# control_master.net
KiCad netlist of a schematic drawn in EAGLE
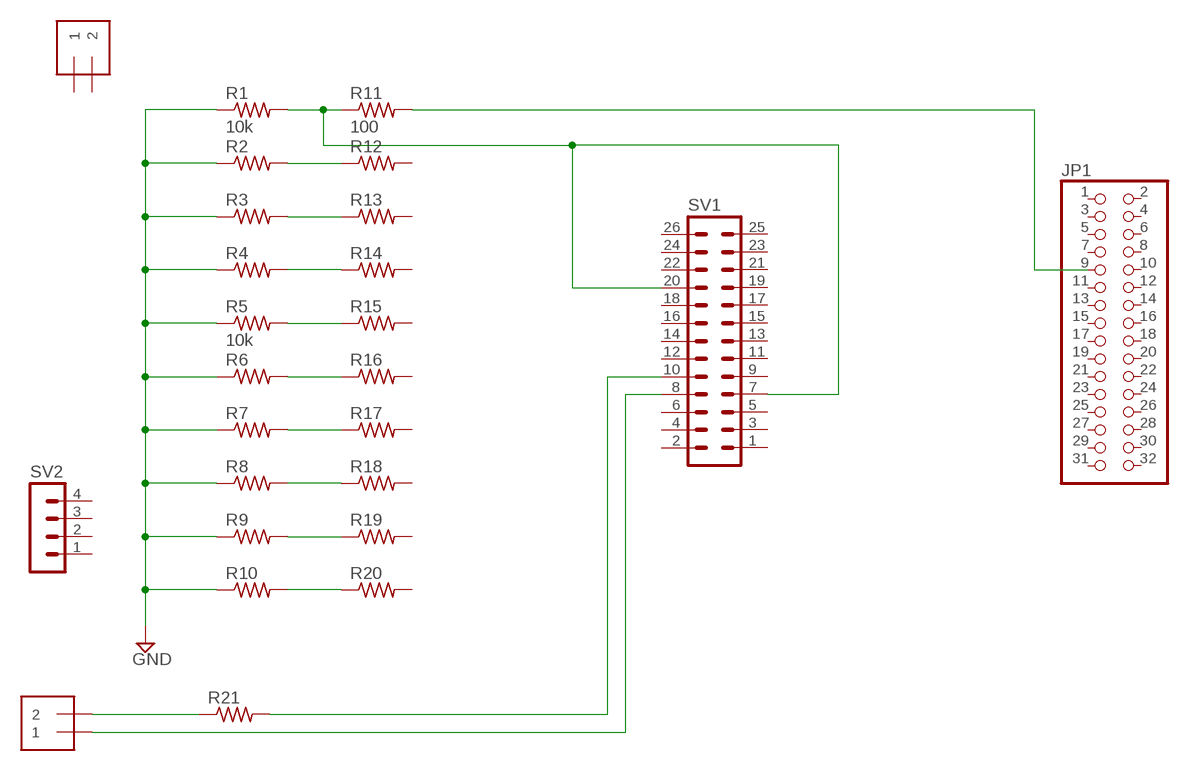
[diagram p0: schematic, sheet 1]

(export (version "E")
  (design (tool "Eeschema 10.0.6"))
  (components
    (comp (ref "J1")
      (value "1X2-3.5MM")
      (footprint "eagle-import:1X2-3.5MM")
      (libsource (lib "eagle-import") (part "1X2-3.5MM"))
    )
    (comp (ref "J2")
      (value "1X2-3.5MM")
      (footprint "eagle-import:1X2-3.5MM")
      (libsource (lib "eagle-import") (part "1X2-3.5MM"))
    )
    (comp (ref "JP1")
      (value "PINHD-2X16")
      (footprint "eagle-import:2X16")
      (libsource (lib "eagle-import") (part "PINHD-2X16"))
    )
    (comp (ref "R1")
      (value "10k")
      (footprint "eagle-import:0207_12")
      (libsource (lib "eagle-import") (part "R-US_0207/12"))
    )
    (comp (ref "R2")
      (value "R-US_0207/12")
      (footprint "eagle-import:0207_12")
      (libsource (lib "eagle-import") (part "R-US_0207/12"))
    )
    (comp (ref "R3")
      (value "R-US_0207/12")
      (footprint "eagle-import:0207_12")
      (libsource (lib "eagle-import") (part "R-US_0207/12"))
    )
    (comp (ref "R4")
      (value "R-US_0207/12")
      (footprint "eagle-import:0207_12")
      (libsource (lib "eagle-import") (part "R-US_0207/12"))
    )
    (comp (ref "R5")
      (value "10k")
      (footprint "eagle-import:0207_12")
      (libsource (lib "eagle-import") (part "R-US_0207/12"))
    )
    (comp (ref "R6")
      (value "R-US_0207/12")
      (footprint "eagle-import:0207_12")
      (libsource (lib "eagle-import") (part "R-US_0207/12"))
    )
    (comp (ref "R7")
      (value "R-US_0207/12")
      (footprint "eagle-import:0207_12")
      (libsource (lib "eagle-import") (part "R-US_0207/12"))
    )
    (comp (ref "R8")
      (value "R-US_0207/12")
      (footprint "eagle-import:0207_12")
      (libsource (lib "eagle-import") (part "R-US_0207/12"))
    )
    (comp (ref "R9")
      (value "R-US_0207/12")
      (footprint "eagle-import:0207_12")
      (libsource (lib "eagle-import") (part "R-US_0207/12"))
    )
    (comp (ref "R10")
      (value "R-US_0207/12")
      (footprint "eagle-import:0207_12")
      (libsource (lib "eagle-import") (part "R-US_0207/12"))
    )
    (comp (ref "R11")
      (value "100")
      (footprint "eagle-import:0207_12")
      (libsource (lib "eagle-import") (part "R-US_0207/12"))
    )
    (comp (ref "R12")
      (value "R-US_0207/12")
      (footprint "eagle-import:0207_12")
      (libsource (lib "eagle-import") (part "R-US_0207/12"))
    )
    (comp (ref "R13")
      (value "R-US_0207/12")
      (footprint "eagle-import:0207_12")
      (libsource (lib "eagle-import") (part "R-US_0207/12"))
    )
    (comp (ref "R14")
      (value "R-US_0207/12")
      (footprint "eagle-import:0207_12")
      (libsource (lib "eagle-import") (part "R-US_0207/12"))
    )
    (comp (ref "R15")
      (value "R-US_0207/12")
      (footprint "eagle-import:0207_12")
      (libsource (lib "eagle-import") (part "R-US_0207/12"))
    )
    (comp (ref "R16")
      (value "R-US_0207/12")
      (footprint "eagle-import:0207_12")
      (libsource (lib "eagle-import") (part "R-US_0207/12"))
    )
    (comp (ref "R17")
      (value "R-US_0207/12")
      (footprint "eagle-import:0207_12")
      (libsource (lib "eagle-import") (part "R-US_0207/12"))
    )
    (comp (ref "R18")
      (value "R-US_0207/12")
      (footprint "eagle-import:0207_12")
      (libsource (lib "eagle-import") (part "R-US_0207/12"))
    )
    (comp (ref "R19")
      (value "R-US_0207/12")
      (footprint "eagle-import:0207_12")
      (libsource (lib "eagle-import") (part "R-US_0207/12"))
    )
    (comp (ref "R20")
      (value "R-US_0207/12")
      (footprint "eagle-import:0207_12")
      (libsource (lib "eagle-import") (part "R-US_0207/12"))
    )
    (comp (ref "R21")
      (value "R-US_0207/12")
      (footprint "eagle-import:0207_12")
      (libsource (lib "eagle-import") (part "R-US_0207/12"))
    )
    (comp (ref "SV1")
      (value "MA13-2")
      (footprint "eagle-import:MA13-2")
      (libsource (lib "eagle-import") (part "MA13-2"))
    )
    (comp (ref "SV2")
      (value "MA04-1")
      (footprint "eagle-import:MA04-1")
      (libsource (lib "eagle-import") (part "MA04-1"))
    )
  )
  (nets
    (net (code "1") (name "GND") (class "Default")
      (node (ref "R1") (pin "1") (pinfunction "1_1") (pintype "passive"))
      (node (ref "R10") (pin "1") (pinfunction "1_1") (pintype "passive"))
      (node (ref "R2") (pin "1") (pinfunction "1_1") (pintype "passive"))
      (node (ref "R3") (pin "1") (pinfunction "1_1") (pintype "passive"))
      (node (ref "R4") (pin "1") (pinfunction "1_1") (pintype "passive"))
      (node (ref "R5") (pin "1") (pinfunction "1_1") (pintype "passive"))
      (node (ref "R6") (pin "1") (pinfunction "1_1") (pintype "passive"))
      (node (ref "R7") (pin "1") (pinfunction "1_1") (pintype "passive"))
      (node (ref "R8") (pin "1") (pinfunction "1_1") (pintype "passive"))
      (node (ref "R9") (pin "1") (pinfunction "1_1") (pintype "passive"))
    )
    (net (code "2") (name "Net-(J1-Pad1)") (class "Default")
      (node (ref "J1") (pin "1") (pinfunction "1_1") (pintype "passive"))
      (node (ref "SV1") (pin "8") (pinfunction "8_8") (pintype "passive"))
    )
    (net (code "3") (name "Net-(J1-Pad2)") (class "Default")
      (node (ref "J1") (pin "2") (pinfunction "2_2") (pintype "passive"))
      (node (ref "R21") (pin "1") (pinfunction "1_1") (pintype "passive"))
    )
    (net (code "4") (name "Net-(JP1-Pad9)") (class "Default")
      (node (ref "JP1") (pin "9") (pinfunction "9_9") (pintype "passive"))
      (node (ref "R11") (pin "2") (pinfunction "2_2") (pintype "passive"))
    )
    (net (code "5") (name "Net-(R1-Pad2)") (class "Default")
      (node (ref "R1") (pin "2") (pinfunction "2_2") (pintype "passive"))
      (node (ref "R11") (pin "1") (pinfunction "1_1") (pintype "passive"))
      (node (ref "SV1") (pin "20") (pinfunction "20_20") (pintype "passive"))
      (node (ref "SV1") (pin "7") (pinfunction "7_7") (pintype "passive"))
    )
    (net (code "6") (name "Net-(R10-Pad2)") (class "Default")
      (node (ref "R10") (pin "2") (pinfunction "2_2") (pintype "passive"))
      (node (ref "R20") (pin "1") (pinfunction "1_1") (pintype "passive"))
    )
    (net (code "7") (name "Net-(R12-Pad1)") (class "Default")
      (node (ref "R12") (pin "1") (pinfunction "1_1") (pintype "passive"))
      (node (ref "R2") (pin "2") (pinfunction "2_2") (pintype "passive"))
    )
    (net (code "8") (name "Net-(R13-Pad1)") (class "Default")
      (node (ref "R13") (pin "1") (pinfunction "1_1") (pintype "passive"))
      (node (ref "R3") (pin "2") (pinfunction "2_2") (pintype "passive"))
    )
    (net (code "9") (name "Net-(R14-Pad1)") (class "Default")
      (node (ref "R14") (pin "1") (pinfunction "1_1") (pintype "passive"))
      (node (ref "R4") (pin "2") (pinfunction "2_2") (pintype "passive"))
    )
    (net (code "10") (name "Net-(R15-Pad1)") (class "Default")
      (node (ref "R15") (pin "1") (pinfunction "1_1") (pintype "passive"))
      (node (ref "R5") (pin "2") (pinfunction "2_2") (pintype "passive"))
    )
    (net (code "11") (name "Net-(R16-Pad1)") (class "Default")
      (node (ref "R16") (pin "1") (pinfunction "1_1") (pintype "passive"))
      (node (ref "R6") (pin "2") (pinfunction "2_2") (pintype "passive"))
    )
    (net (code "12") (name "Net-(R17-Pad1)") (class "Default")
      (node (ref "R17") (pin "1") (pinfunction "1_1") (pintype "passive"))
      (node (ref "R7") (pin "2") (pinfunction "2_2") (pintype "passive"))
    )
    (net (code "13") (name "Net-(R18-Pad1)") (class "Default")
      (node (ref "R18") (pin "1") (pinfunction "1_1") (pintype "passive"))
      (node (ref "R8") (pin "2") (pinfunction "2_2") (pintype "passive"))
    )
    (net (code "14") (name "Net-(R19-Pad1)") (class "Default")
      (node (ref "R19") (pin "1") (pinfunction "1_1") (pintype "passive"))
      (node (ref "R9") (pin "2") (pinfunction "2_2") (pintype "passive"))
    )
    (net (code "15") (name "Net-(R21-Pad2)") (class "Default")
      (node (ref "R21") (pin "2") (pinfunction "2_2") (pintype "passive"))
      (node (ref "SV1") (pin "10") (pinfunction "10_10") (pintype "passive"))
    )
    (net (code "16") (name "unconnected-(J2-Pad1)") (class "Default")
      (node (ref "J2") (pin "1") (pinfunction "1_1") (pintype "passive"))
    )
    (net (code "17") (name "unconnected-(J2-Pad2)") (class "Default")
      (node (ref "J2") (pin "2") (pinfunction "2_2") (pintype "passive"))
    )
    (net (code "18") (name "unconnected-(JP1-Pad1)") (class "Default")
      (node (ref "JP1") (pin "1") (pinfunction "1_1") (pintype "passive"))
    )
    (net (code "19") (name "unconnected-(JP1-Pad2)") (class "Default")
      (node (ref "JP1") (pin "2") (pinfunction "2_2") (pintype "passive"))
    )
    (net (code "20") (name "unconnected-(JP1-Pad3)") (class "Default")
      (node (ref "JP1") (pin "3") (pinfunction "3_3") (pintype "passive"))
    )
    (net (code "21") (name "unconnected-(JP1-Pad4)") (class "Default")
      (node (ref "JP1") (pin "4") (pinfunction "4_4") (pintype "passive"))
    )
    (net (code "22") (name "unconnected-(JP1-Pad5)") (class "Default")
      (node (ref "JP1") (pin "5") (pinfunction "5_5") (pintype "passive"))
    )
    (net (code "23") (name "unconnected-(JP1-Pad6)") (class "Default")
      (node (ref "JP1") (pin "6") (pinfunction "6_6") (pintype "passive"))
    )
    (net (code "24") (name "unconnected-(JP1-Pad7)") (class "Default")
      (node (ref "JP1") (pin "7") (pinfunction "7_7") (pintype "passive"))
    )
    (net (code "25") (name "unconnected-(JP1-Pad8)") (class "Default")
      (node (ref "JP1") (pin "8") (pinfunction "8_8") (pintype "passive"))
    )
    (net (code "26") (name "unconnected-(JP1-Pad10)") (class "Default")
      (node (ref "JP1") (pin "10") (pinfunction "10_10") (pintype "passive"))
    )
    (net (code "27") (name "unconnected-(JP1-Pad11)") (class "Default")
      (node (ref "JP1") (pin "11") (pinfunction "11_11") (pintype "passive"))
    )
    (net (code "28") (name "unconnected-(JP1-Pad12)") (class "Default")
      (node (ref "JP1") (pin "12") (pinfunction "12_12") (pintype "passive"))
    )
    (net (code "29") (name "unconnected-(JP1-Pad13)") (class "Default")
      (node (ref "JP1") (pin "13") (pinfunction "13_13") (pintype "passive"))
    )
    (net (code "30") (name "unconnected-(JP1-Pad14)") (class "Default")
      (node (ref "JP1") (pin "14") (pinfunction "14_14") (pintype "passive"))
    )
    (net (code "31") (name "unconnected-(JP1-Pad15)") (class "Default")
      (node (ref "JP1") (pin "15") (pinfunction "15_15") (pintype "passive"))
    )
    (net (code "32") (name "unconnected-(JP1-Pad16)") (class "Default")
      (node (ref "JP1") (pin "16") (pinfunction "16_16") (pintype "passive"))
    )
    (net (code "33") (name "unconnected-(JP1-Pad17)") (class "Default")
      (node (ref "JP1") (pin "17") (pinfunction "17_17") (pintype "passive"))
    )
    (net (code "34") (name "unconnected-(JP1-Pad18)") (class "Default")
      (node (ref "JP1") (pin "18") (pinfunction "18_18") (pintype "passive"))
    )
    (net (code "35") (name "unconnected-(JP1-Pad19)") (class "Default")
      (node (ref "JP1") (pin "19") (pinfunction "19_19") (pintype "passive"))
    )
    (net (code "36") (name "unconnected-(JP1-Pad20)") (class "Default")
      (node (ref "JP1") (pin "20") (pinfunction "20_20") (pintype "passive"))
    )
    (net (code "37") (name "unconnected-(JP1-Pad21)") (class "Default")
      (node (ref "JP1") (pin "21") (pinfunction "21_21") (pintype "passive"))
    )
    (net (code "38") (name "unconnected-(JP1-Pad22)") (class "Default")
      (node (ref "JP1") (pin "22") (pinfunction "22_22") (pintype "passive"))
    )
    (net (code "39") (name "unconnected-(JP1-Pad23)") (class "Default")
      (node (ref "JP1") (pin "23") (pinfunction "23_23") (pintype "passive"))
    )
    (net (code "40") (name "unconnected-(JP1-Pad24)") (class "Default")
      (node (ref "JP1") (pin "24") (pinfunction "24_24") (pintype "passive"))
    )
    (net (code "41") (name "unconnected-(JP1-Pad25)") (class "Default")
      (node (ref "JP1") (pin "25") (pinfunction "25_25") (pintype "passive"))
    )
    (net (code "42") (name "unconnected-(JP1-Pad26)") (class "Default")
      (node (ref "JP1") (pin "26") (pinfunction "26_26") (pintype "passive"))
    )
    (net (code "43") (name "unconnected-(JP1-Pad27)") (class "Default")
      (node (ref "JP1") (pin "27") (pinfunction "27_27") (pintype "passive"))
    )
    (net (code "44") (name "unconnected-(JP1-Pad28)") (class "Default")
      (node (ref "JP1") (pin "28") (pinfunction "28_28") (pintype "passive"))
    )
    (net (code "45") (name "unconnected-(JP1-Pad29)") (class "Default")
      (node (ref "JP1") (pin "29") (pinfunction "29_29") (pintype "passive"))
    )
    (net (code "46") (name "unconnected-(JP1-Pad30)") (class "Default")
      (node (ref "JP1") (pin "30") (pinfunction "30_30") (pintype "passive"))
    )
    (net (code "47") (name "unconnected-(JP1-Pad31)") (class "Default")
      (node (ref "JP1") (pin "31") (pinfunction "31_31") (pintype "passive"))
    )
    (net (code "48") (name "unconnected-(JP1-Pad32)") (class "Default")
      (node (ref "JP1") (pin "32") (pinfunction "32_32") (pintype "passive"))
    )
    (net (code "49") (name "unconnected-(R12-Pad2)") (class "Default")
      (node (ref "R12") (pin "2") (pinfunction "2_2") (pintype "passive"))
    )
    (net (code "50") (name "unconnected-(R13-Pad2)") (class "Default")
      (node (ref "R13") (pin "2") (pinfunction "2_2") (pintype "passive"))
    )
    (net (code "51") (name "unconnected-(R14-Pad2)") (class "Default")
      (node (ref "R14") (pin "2") (pinfunction "2_2") (pintype "passive"))
    )
    (net (code "52") (name "unconnected-(R15-Pad2)") (class "Default")
      (node (ref "R15") (pin "2") (pinfunction "2_2") (pintype "passive"))
    )
    (net (code "53") (name "unconnected-(R16-Pad2)") (class "Default")
      (node (ref "R16") (pin "2") (pinfunction "2_2") (pintype "passive"))
    )
    (net (code "54") (name "unconnected-(R17-Pad2)") (class "Default")
      (node (ref "R17") (pin "2") (pinfunction "2_2") (pintype "passive"))
    )
    (net (code "55") (name "unconnected-(R18-Pad2)") (class "Default")
      (node (ref "R18") (pin "2") (pinfunction "2_2") (pintype "passive"))
    )
    (net (code "56") (name "unconnected-(R19-Pad2)") (class "Default")
      (node (ref "R19") (pin "2") (pinfunction "2_2") (pintype "passive"))
    )
    (net (code "57") (name "unconnected-(R20-Pad2)") (class "Default")
      (node (ref "R20") (pin "2") (pinfunction "2_2") (pintype "passive"))
    )
    (net (code "58") (name "unconnected-(SV1-Pad1)") (class "Default")
      (node (ref "SV1") (pin "1") (pinfunction "1_1") (pintype "passive"))
    )
    (net (code "59") (name "unconnected-(SV1-Pad2)") (class "Default")
      (node (ref "SV1") (pin "2") (pinfunction "2_2") (pintype "passive"))
    )
    (net (code "60") (name "unconnected-(SV1-Pad3)") (class "Default")
      (node (ref "SV1") (pin "3") (pinfunction "3_3") (pintype "passive"))
    )
    (net (code "61") (name "unconnected-(SV1-Pad4)") (class "Default")
      (node (ref "SV1") (pin "4") (pinfunction "4_4") (pintype "passive"))
    )
    (net (code "62") (name "unconnected-(SV1-Pad5)") (class "Default")
      (node (ref "SV1") (pin "5") (pinfunction "5_5") (pintype "passive"))
    )
    (net (code "63") (name "unconnected-(SV1-Pad6)") (class "Default")
      (node (ref "SV1") (pin "6") (pinfunction "6_6") (pintype "passive"))
    )
    (net (code "64") (name "unconnected-(SV1-Pad9)") (class "Default")
      (node (ref "SV1") (pin "9") (pinfunction "9_9") (pintype "passive"))
    )
    (net (code "65") (name "unconnected-(SV1-Pad11)") (class "Default")
      (node (ref "SV1") (pin "11") (pinfunction "11_11") (pintype "passive"))
    )
    (net (code "66") (name "unconnected-(SV1-Pad12)") (class "Default")
      (node (ref "SV1") (pin "12") (pinfunction "12_12") (pintype "passive"))
    )
    (net (code "67") (name "unconnected-(SV1-Pad13)") (class "Default")
      (node (ref "SV1") (pin "13") (pinfunction "13_13") (pintype "passive"))
    )
    (net (code "68") (name "unconnected-(SV1-Pad14)") (class "Default")
      (node (ref "SV1") (pin "14") (pinfunction "14_14") (pintype "passive"))
    )
    (net (code "69") (name "unconnected-(SV1-Pad15)") (class "Default")
      (node (ref "SV1") (pin "15") (pinfunction "15_15") (pintype "passive"))
    )
    (net (code "70") (name "unconnected-(SV1-Pad16)") (class "Default")
      (node (ref "SV1") (pin "16") (pinfunction "16_16") (pintype "passive"))
    )
    (net (code "71") (name "unconnected-(SV1-Pad17)") (class "Default")
      (node (ref "SV1") (pin "17") (pinfunction "17_17") (pintype "passive"))
    )
    (net (code "72") (name "unconnected-(SV1-Pad18)") (class "Default")
      (node (ref "SV1") (pin "18") (pinfunction "18_18") (pintype "passive"))
    )
    (net (code "73") (name "unconnected-(SV1-Pad19)") (class "Default")
      (node (ref "SV1") (pin "19") (pinfunction "19_19") (pintype "passive"))
    )
    (net (code "74") (name "unconnected-(SV1-Pad21)") (class "Default")
      (node (ref "SV1") (pin "21") (pinfunction "21_21") (pintype "passive"))
    )
    (net (code "75") (name "unconnected-(SV1-Pad22)") (class "Default")
      (node (ref "SV1") (pin "22") (pinfunction "22_22") (pintype "passive"))
    )
    (net (code "76") (name "unconnected-(SV1-Pad23)") (class "Default")
      (node (ref "SV1") (pin "23") (pinfunction "23_23") (pintype "passive"))
    )
    (net (code "77") (name "unconnected-(SV1-Pad24)") (class "Default")
      (node (ref "SV1") (pin "24") (pinfunction "24_24") (pintype "passive"))
    )
    (net (code "78") (name "unconnected-(SV1-Pad25)") (class "Default")
      (node (ref "SV1") (pin "25") (pinfunction "25_25") (pintype "passive"))
    )
    (net (code "79") (name "unconnected-(SV1-Pad26)") (class "Default")
      (node (ref "SV1") (pin "26") (pinfunction "26_26") (pintype "passive"))
    )
    (net (code "80") (name "unconnected-(SV2-Pad1)") (class "Default")
      (node (ref "SV2") (pin "1") (pinfunction "1_1") (pintype "passive"))
    )
    (net (code "81") (name "unconnected-(SV2-Pad2)") (class "Default")
      (node (ref "SV2") (pin "2") (pinfunction "2_2") (pintype "passive"))
    )
    (net (code "82") (name "unconnected-(SV2-Pad3)") (class "Default")
      (node (ref "SV2") (pin "3") (pinfunction "3_3") (pintype "passive"))
    )
    (net (code "83") (name "unconnected-(SV2-Pad4)") (class "Default")
      (node (ref "SV2") (pin "4") (pinfunction "4_4") (pintype "passive"))
    )
  )
)
